# TSAC_Logic.net
KiCad netlist of a schematic drawn in Altium Designer
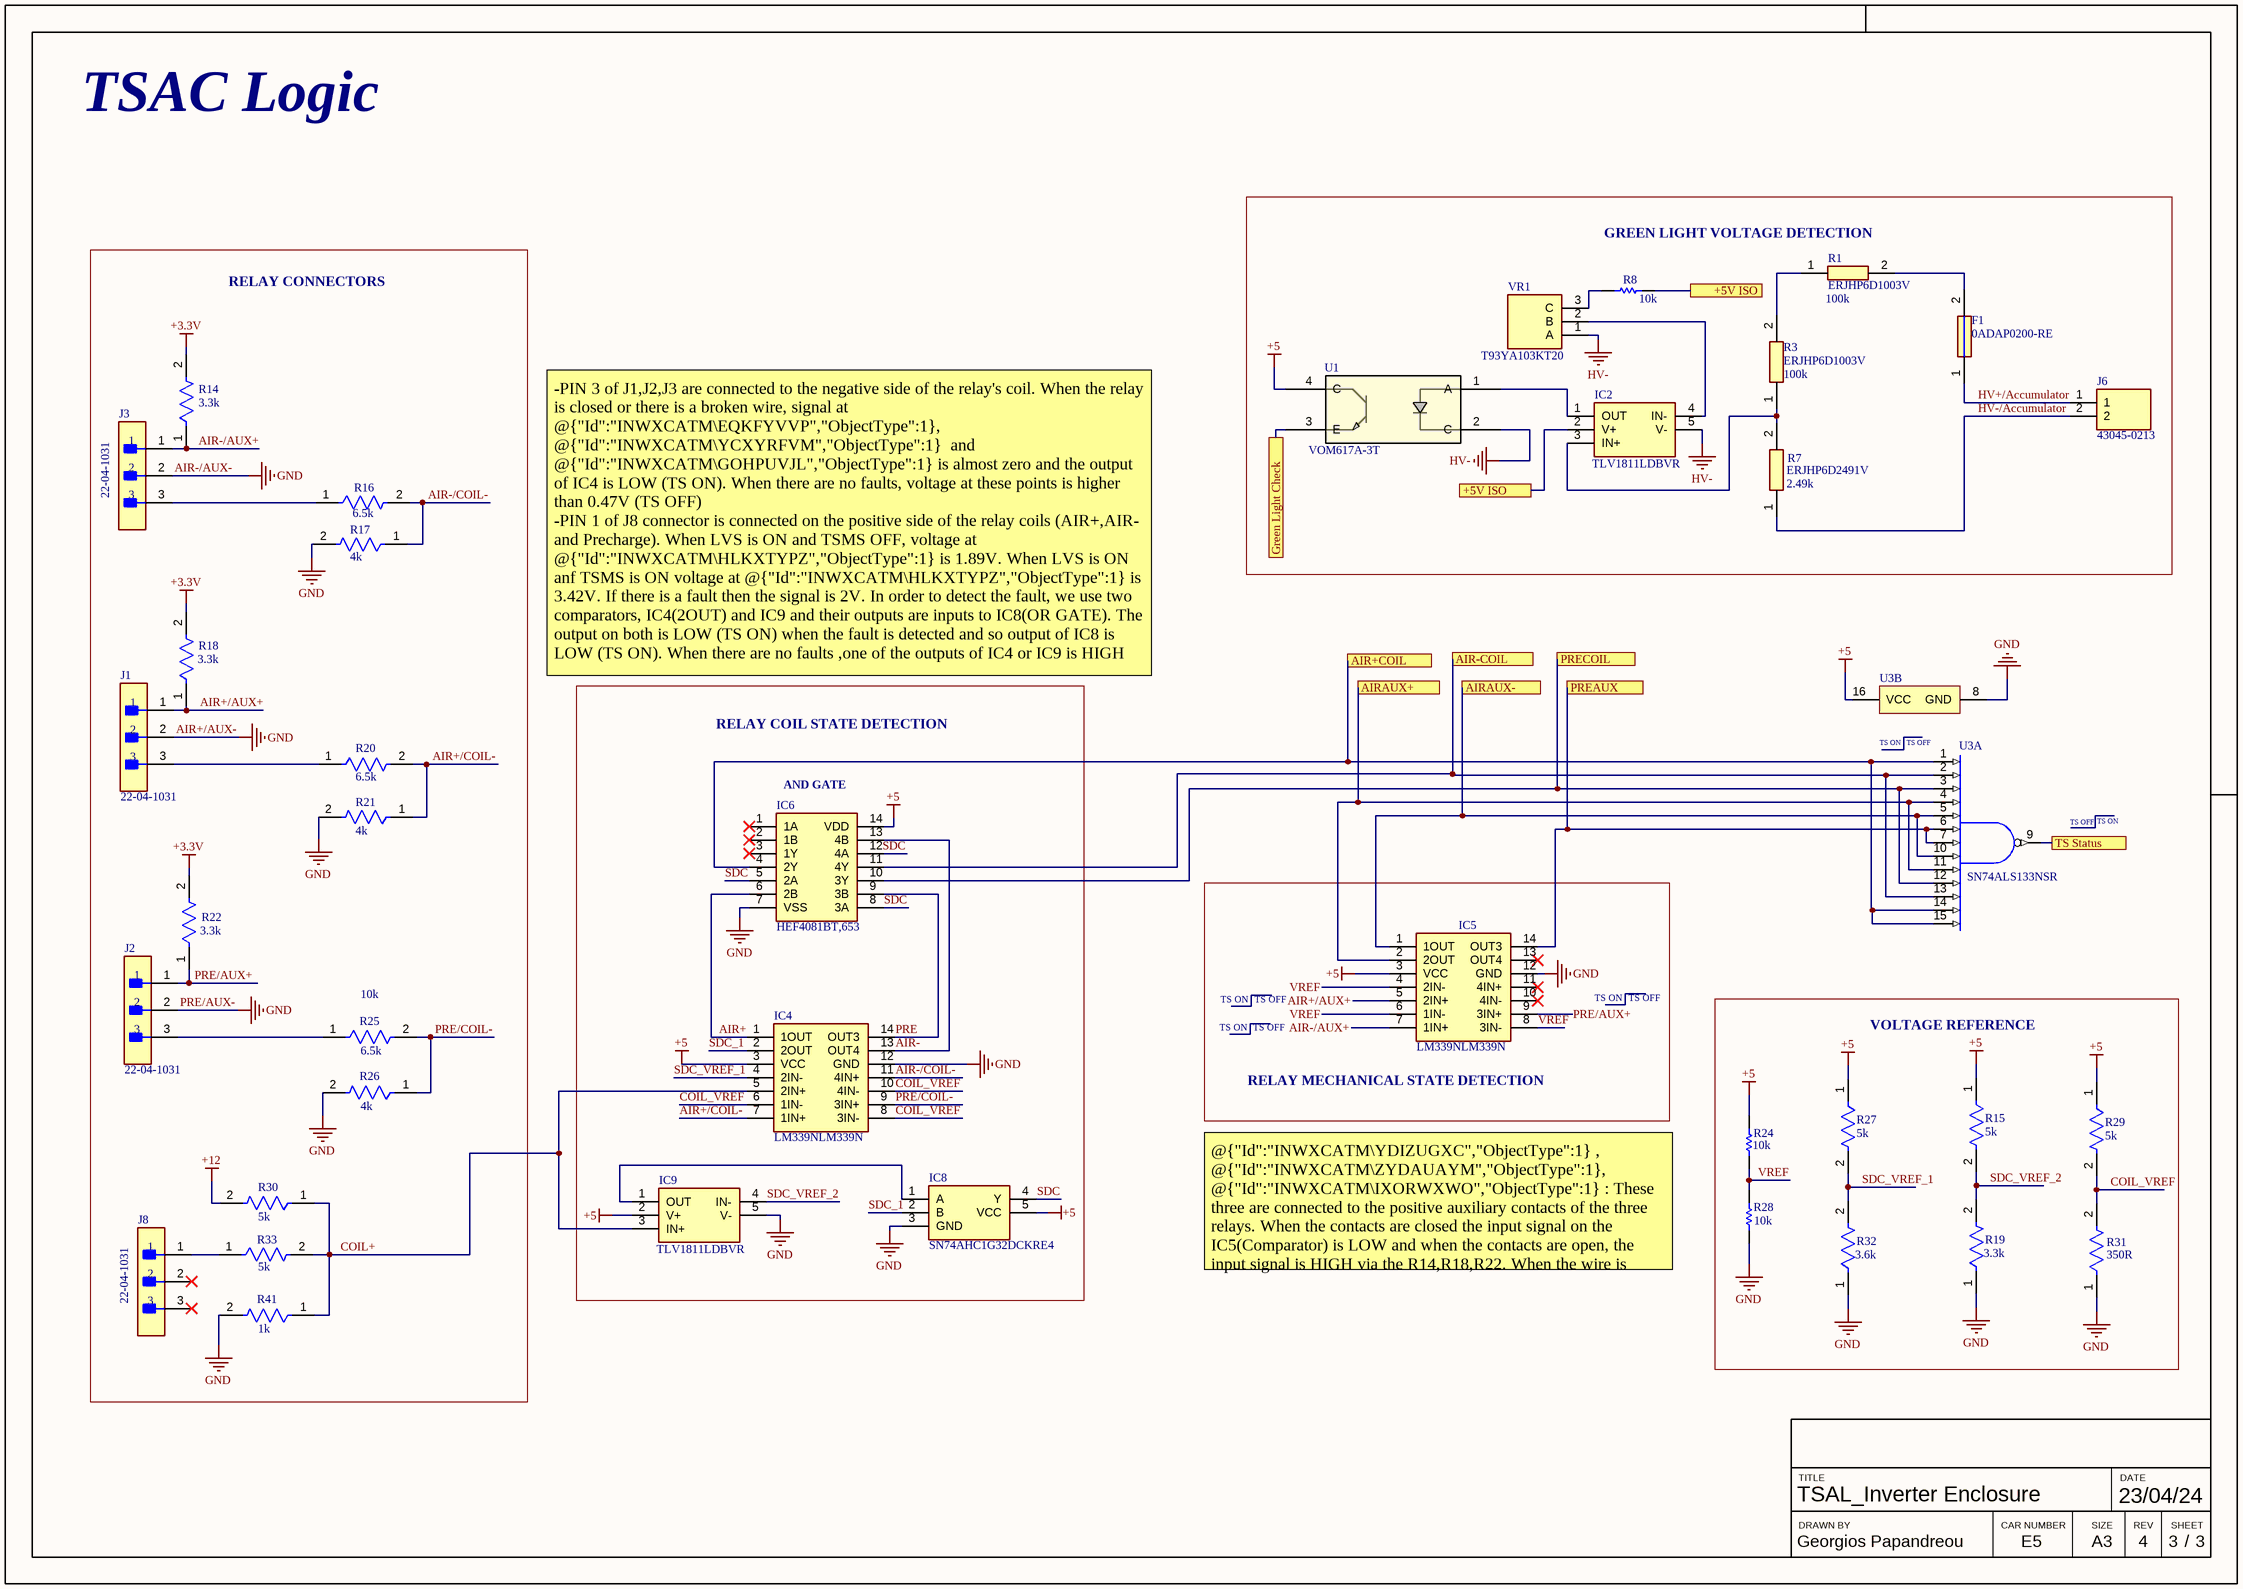
[diagram p0: TSAC_Logic.SchDoc]

(export (version "E")
  (design (tool "Eeschema 10.0.6"))
  (components
    (comp (ref "F1")
      (value "0ADAP0200-RE")
      (footprint "SamacSys:0ADAP0200RE")
      (description "Fuse")
      (fields (field (name "MOUSER PART NUMBER") "530-0ADAP0200-RE"))
      (libsource (lib "*") (part "0ADAP0200-RE"))
    )
    (comp (ref "IC2")
      (value "TLV1811LDBVR")
      (footprint "SamacSys:SOT95P280X145-5N")
      (description "Integrated Circuit")
      (fields (field (name "MOUSER PART NUMBER") "595-TLV1811LDBVR"))
      (libsource (lib "*") (part "TLV1811LDBVR"))
    )
    (comp (ref "IC4")
      (value "LM339NLM339N")
      (footprint "SamacSys:DIP794W53P254L1930H508Q14N")
      (description "Integrated Circuit")
      (fields
        (field (name "MANUFACTURER_PART_NUMBER") "LM339N")
        (field (name "MOUSER PART NUMBER") "595-LM339N")
      )
      (libsource (lib "*") (part "LM339N"))
    )
    (comp (ref "IC5")
      (value "LM339NLM339N")
      (footprint "SamacSys:DIP794W53P254L1930H508Q14N")
      (description "Integrated Circuit")
      (fields
        (field (name "MANUFACTURER_PART_NUMBER") "LM339N")
        (field (name "MOUSER PART NUMBER") "595-LM339N")
      )
      (libsource (lib "*") (part "LM339N"))
    )
    (comp (ref "IC6")
      (value "HEF4081BT,653")
      (footprint "SamacSys:SOIC127P600X175-14N")
      (description "Integrated Circuit")
      (fields (field (name "MOUSER PART NUMBER") "771-HEF4081BTD-T"))
      (libsource (lib "*") (part "HEF4081BT,653"))
    )
    (comp (ref "IC8")
      (value "SN74AHC1G32DCKRE4")
      (footprint "SamacSys:SOT65P210X110-5N")
      (description "Integrated Circuit")
      (fields (field (name "MOUSER PART NUMBER") "595-74AHC1G32DCKRE4"))
      (libsource (lib "*") (part "SN74AHC1G32DCKRE4"))
    )
    (comp (ref "IC9")
      (value "TLV1811LDBVR")
      (footprint "SamacSys:SOT95P280X145-5N")
      (description "Integrated Circuit")
      (fields (field (name "MOUSER PART NUMBER") "595-TLV1811LDBVR"))
      (libsource (lib "*") (part "TLV1811LDBVR"))
    )
    (comp (ref "J1")
      (value "22-04-1031")
      (footprint "FP-22-04-1031-MFG")
      (description "CONN HEADER VERT 3POS 2.5MM")
      (libsource (lib "Altium Content Vault") (part "0d3f023dd272f625e17a2be33dea85f"))
    )
    (comp (ref "J2")
      (value "22-04-1031")
      (footprint "FP-22-04-1031-MFG")
      (description "CONN HEADER VERT 3POS 2.5MM")
      (libsource (lib "Altium Content Vault") (part "0d3f023dd272f625e17a2be33dea85f"))
    )
    (comp (ref "J3")
      (value "22-04-1031")
      (footprint "FP-22-04-1031-MFG")
      (description "CONN HEADER VERT 3POS 2.5MM")
      (libsource (lib "Altium Content Vault") (part "0d3f023dd272f625e17a2be33dea85f"))
    )
    (comp (ref "J6")
      (value "43045-0213")
      (footprint "SamacSys:43045-02YY_121314")
      (description "Connector")
      (fields (field (name "MOUSER PART NUMBER") "538-43045-0213"))
      (libsource (lib "*") (part "43045-0213"))
    )
    (comp (ref "J8")
      (value "22-04-1031")
      (footprint "FP-22-04-1031-MFG")
      (description "CONN HEADER VERT 3POS 2.5MM")
      (libsource (lib "Altium Content Vault") (part "0d3f023dd272f625e17a2be33dea85f"))
    )
    (comp (ref "R1")
      (value "ERJHP6D1003V")
      (footprint "SamacSys:ERJHP6D1000V")
      (description "Resistor")
      (libsource (lib "") (part "ERJHP6D1003V_1"))
    )
    (comp (ref "R3")
      (value "ERJHP6D1003V")
      (footprint "SamacSys:ERJHP6D1000V")
      (description "Resistor")
      (libsource (lib "*") (part "ERJHP6D1003V"))
    )
    (comp (ref "R7")
      (value "ERJHP6D2491V")
      (footprint "SamacSys:ERJHP6D1000V")
      (description "Resistor")
      (libsource (lib "*") (part "ERJHP6D2491V"))
    )
    (comp (ref "R8")
      (value "CRCW080510K0FKEC")
      (footprint "RESC2013X50X30ML20T20")
      (fields (field (name "MANUFACTURER") "Vishay Dale"))
      (libsource (lib "Altium Content Vault") (part "RES"))
    )
    (comp (ref "R14")
      (value "CRCW08053K30FKEC")
      (footprint "FP-CRCW0805-e3-MFG")
      (description "RES Thick Film, 3.3kΩ, 1%, 0.125W, 100ppm/°C, 0805")
      (fields (field (name "TOLERANCE") "1%"))
      (libsource (lib "Altium Content Vault") (part "1029c3af85768c4190bb7ad29bc67b5"))
    )
    (comp (ref "R15")
      (value "CRCW080520K0JNEB")
      (footprint "FP-CRCW0805-e3-IPC_B")
      (description "RES Thick Film, 20kΩ, 5%, 0.125W, 200ppm/°C, 0805")
      (fields (field (name "TOLERANCE") "5%"))
      (libsource (lib "Altium Content Vault") (part "1029c3af85768c4190bb7ad29bc67b5"))
    )
    (comp (ref "R16")
      (value "CRCW120610K0FKEA")
      (footprint "FP-CRCW1206-e3-IPC_C")
      (description "RES Thick Film, 10kΩ, 1%, 0.25W, 100ppm/°C, 1206")
      (fields (field (name "TOLERANCE") "1%"))
      (libsource (lib "Altium Content Vault") (part "1029c3af85768c4190bb7ad29bc67b5"))
    )
    (comp (ref "R17")
      (value "RN732BTTD4001B25")
      (footprint "FP-RN732B-IPC_C")
      (description "4kΩ ±0.1% 0.125W, 1/8W Chip Resistor 1206 (3216 Metric) Moisture Resistant Thin Film")
      (fields (field (name "TOLERANCE") "0.1%"))
      (libsource (lib "Altium Content Vault") (part "1029c3af85768c4190bb7ad29bc67b5"))
    )
    (comp (ref "R18")
      (value "CRCW08053K30FKEC")
      (footprint "FP-CRCW0805-e3-MFG")
      (description "RES Thick Film, 3.3kΩ, 1%, 0.125W, 100ppm/°C, 0805")
      (fields (field (name "TOLERANCE") "1%"))
      (libsource (lib "Altium Content Vault") (part "1029c3af85768c4190bb7ad29bc67b5"))
    )
    (comp (ref "R19")
      (value "CRCW120610K0FKEA")
      (footprint "FP-CRCW1206-e3-IPC_C")
      (description "RES Thick Film, 10kΩ, 1%, 0.25W, 100ppm/°C, 1206")
      (fields (field (name "TOLERANCE") "1%"))
      (libsource (lib "Altium Content Vault") (part "1029c3af85768c4190bb7ad29bc67b5"))
    )
    (comp (ref "R20")
      (value "CRCW120610K0FKEA")
      (footprint "FP-CRCW1206-e3-IPC_C")
      (description "RES Thick Film, 10kΩ, 1%, 0.25W, 100ppm/°C, 1206")
      (fields (field (name "TOLERANCE") "1%"))
      (libsource (lib "Altium Content Vault") (part "1029c3af85768c4190bb7ad29bc67b5"))
    )
    (comp (ref "R21")
      (value "RN732BTTD4001B25")
      (footprint "FP-RN732B-IPC_C")
      (description "4kΩ ±0.1% 0.125W, 1/8W Chip Resistor 1206 (3216 Metric) Moisture Resistant Thin Film")
      (fields (field (name "TOLERANCE") "0.1%"))
      (libsource (lib "Altium Content Vault") (part "1029c3af85768c4190bb7ad29bc67b5"))
    )
    (comp (ref "R22")
      (value "CRCW08053K30FKEC")
      (footprint "FP-CRCW0805-e3-MFG")
      (description "RES Thick Film, 3.3kΩ, 1%, 0.125W, 100ppm/°C, 0805")
      (fields (field (name "TOLERANCE") "1%"))
      (libsource (lib "Altium Content Vault") (part "1029c3af85768c4190bb7ad29bc67b5"))
    )
    (comp (ref "R24")
      (value "CRCW080510K0FKEC")
      (footprint "RESC2013X50X30ML20T20")
      (fields (field (name "MANUFACTURER") "Vishay Dale"))
      (libsource (lib "Altium Content Vault") (part "RES"))
    )
    (comp (ref "R25")
      (value "CRCW120610K0FKEA")
      (footprint "FP-CRCW1206-e3-IPC_C")
      (description "RES Thick Film, 10kΩ, 1%, 0.25W, 100ppm/°C, 1206")
      (fields (field (name "TOLERANCE") "1%"))
      (libsource (lib "Altium Content Vault") (part "1029c3af85768c4190bb7ad29bc67b5"))
    )
    (comp (ref "R26")
      (value "RN732BTTD4001B25")
      (footprint "FP-RN732B-IPC_C")
      (description "4kΩ ±0.1% 0.125W, 1/8W Chip Resistor 1206 (3216 Metric) Moisture Resistant Thin Film")
      (fields (field (name "TOLERANCE") "0.1%"))
      (libsource (lib "Altium Content Vault") (part "1029c3af85768c4190bb7ad29bc67b5"))
    )
    (comp (ref "R27")
      (value "CRCW080520K0JNEB")
      (footprint "FP-CRCW0805-e3-IPC_B")
      (description "RES Thick Film, 20kΩ, 5%, 0.125W, 200ppm/°C, 0805")
      (fields (field (name "TOLERANCE") "5%"))
      (libsource (lib "Altium Content Vault") (part "1029c3af85768c4190bb7ad29bc67b5"))
    )
    (comp (ref "R28")
      (value "CRCW080510K0FKEC")
      (footprint "RESC2013X50X30ML20T20")
      (fields (field (name "MANUFACTURER") "Vishay Dale"))
      (libsource (lib "Altium Content Vault") (part "RES"))
    )
    (comp (ref "R29")
      (value "CRCW080520K0JNEB")
      (footprint "FP-CRCW0805-e3-IPC_B")
      (description "RES Thick Film, 20kΩ, 5%, 0.125W, 200ppm/°C, 0805")
      (fields (field (name "TOLERANCE") "5%"))
      (libsource (lib "Altium Content Vault") (part "1029c3af85768c4190bb7ad29bc67b5"))
    )
    (comp (ref "R30")
      (value "CRCW080520K0JNEB")
      (footprint "FP-CRCW0805-e3-IPC_B")
      (description "RES Thick Film, 20kΩ, 5%, 0.125W, 200ppm/°C, 0805")
      (fields (field (name "TOLERANCE") "5%"))
      (libsource (lib "Altium Content Vault") (part "1029c3af85768c4190bb7ad29bc67b5"))
    )
    (comp (ref "R31")
      (value "MCA12060D8000BP500")
      (footprint "FP-MCA1206-IPC_C")
      (description "Res MC Precision Thin Film 1206 800Ω 0.1% 0.25W ±25ppm/°C Molded Paper T/R")
      (fields (field (name "TOLERANCE") "0.1%"))
      (libsource (lib "Altium Content Vault") (part "1029c3af85768c4190bb7ad29bc67b5"))
    )
    (comp (ref "R32")
      (value "CRCW120610K0FKEA")
      (footprint "FP-CRCW1206-e3-IPC_C")
      (description "RES Thick Film, 10kΩ, 1%, 0.25W, 100ppm/°C, 1206")
      (fields (field (name "TOLERANCE") "1%"))
      (libsource (lib "Altium Content Vault") (part "1029c3af85768c4190bb7ad29bc67b5"))
    )
    (comp (ref "R33")
      (value "CRCW120610K0FKEA")
      (footprint "FP-CRCW1206-e3-IPC_C")
      (description "RES Thick Film, 10kΩ, 1%, 0.25W, 100ppm/°C, 1206")
      (fields (field (name "TOLERANCE") "1%"))
      (libsource (lib "Altium Content Vault") (part "1029c3af85768c4190bb7ad29bc67b5"))
    )
    (comp (ref "R41")
      (value "RN732BTTD4001B25")
      (footprint "FP-RN732B-IPC_C")
      (description "4kΩ ±0.1% 0.125W, 1/8W Chip Resistor 1206 (3216 Metric) Moisture Resistant Thin Film")
      (fields (field (name "TOLERANCE") "0.1%"))
      (libsource (lib "Altium Content Vault") (part "1029c3af85768c4190bb7ad29bc67b5"))
    )
    (comp (ref "U1")
      (value "VOM617A-3T")
      (footprint "SMD-4_VOM617A_VIS")
      (description "VOM617A-3T Transistor Output Optocoupler, 1-Element, 3750V Isolation")
      (libsource (lib "Altium Content Vault") (part "VOM617A-3T"))
    )
    (comp (ref "U3")
      (value "SN74ALS133NSR")
      (footprint "NS0016A_M")
      (description "13-Input Positive-NAND Gates, NS0016A, LARGE T&R")
      (fields
        (field (name "GENERIC PART NUMBER") "SN74ALS133")
        (field (name "MANUFACTURER") "Texas Instruments")
      )
      (libsource (lib "Altium Content Vault") (part "TI-SNX4ALS133-16"))
    )
    (comp (ref "VR1")
      (value "T93YA103KT20")
      (footprint "SamacSys:T93YA5K10")
      (description "Variable Resistor")
      (fields (field (name "MOUSER PART NUMBER") "72-T93YA-10K"))
      (libsource (lib "*") (part "T93YA103KT20"))
    )
  )
  (nets
    (net (code "1") (name "+3.3V") (class "Default")
      (node (ref "R14") (pin "2") (pinfunction "2_2") (pintype "passive"))
      (node (ref "R18") (pin "2") (pinfunction "2_2") (pintype "passive"))
      (node (ref "R22") (pin "2") (pinfunction "2_2") (pintype "passive"))
    )
    (net (code "2") (name "+5") (class "Default")
      (node (ref "IC4") (pin "3") (pinfunction "VCC_3") (pintype "passive"))
      (node (ref "IC5") (pin "3") (pinfunction "VCC_3") (pintype "passive"))
      (node (ref "IC6") (pin "14") (pinfunction "VDD_14") (pintype "passive"))
      (node (ref "IC8") (pin "5") (pinfunction "VCC_5") (pintype "passive"))
      (node (ref "IC9") (pin "2") (pinfunction "V+_2") (pintype "passive"))
      (node (ref "R15") (pin "1") (pinfunction "1_1") (pintype "passive"))
      (node (ref "R24") (pin "2") (pinfunction "2_2") (pintype "passive"))
      (node (ref "R27") (pin "1") (pinfunction "1_1") (pintype "passive"))
      (node (ref "R29") (pin "1") (pinfunction "1_1") (pintype "passive"))
      (node (ref "U1") (pin "4") (pinfunction "C_4") (pintype "passive"))
      (node (ref "U3") (pin "16") (pinfunction "VCC_16") (pintype "power_in"))
    )
    (net (code "3") (name "+12") (class "Default")
      (node (ref "R30") (pin "2") (pinfunction "2_2") (pintype "passive"))
    )
    (net (code "4") (name "/+5V ISO") (class "Default")
      (node (ref "IC2") (pin "2") (pinfunction "V+_2") (pintype "passive"))
      (node (ref "R8") (pin "1") (pinfunction "1_1") (pintype "passive"))
    )
    (net (code "5") (name "/AIR+") (class "Default")
      (node (ref "IC4") (pin "1") (pinfunction "1OUT_1") (pintype "passive"))
      (node (ref "IC6") (pin "6") (pinfunction "2B_6") (pintype "passive"))
    )
    (net (code "6") (name "/AIR+COIL") (class "Default")
      (node (ref "IC6") (pin "4") (pinfunction "2Y_4") (pintype "passive"))
      (node (ref "U3") (pin "1") (pinfunction "A_1") (pintype "input"))
      (node (ref "U3") (pin "14") (pinfunction "L_14") (pintype "input"))
      (node (ref "U3") (pin "15") (pinfunction "M_15") (pintype "input"))
    )
    (net (code "7") (name "/AIR+{slash}AUX+") (class "Default")
      (node (ref "IC5") (pin "5") (pinfunction "2IN+_5") (pintype "passive"))
      (node (ref "J1") (pin "1") (pinfunction "1_1") (pintype "passive"))
      (node (ref "R18") (pin "1") (pinfunction "1_1") (pintype "passive"))
    )
    (net (code "8") (name "/AIR+{slash}COIL-") (class "Default")
      (node (ref "IC4") (pin "7") (pinfunction "1IN+_7") (pintype "passive"))
      (node (ref "R20") (pin "2") (pinfunction "2_2") (pintype "passive"))
      (node (ref "R21") (pin "1") (pinfunction "1_1") (pintype "passive"))
    )
    (net (code "9") (name "/AIR-") (class "Default")
      (node (ref "IC4") (pin "13") (pinfunction "OUT4_13") (pintype "passive"))
      (node (ref "IC6") (pin "13") (pinfunction "4B_13") (pintype "passive"))
    )
    (net (code "10") (name "/AIR-COIL") (class "Default")
      (node (ref "IC6") (pin "11") (pinfunction "4Y_11") (pintype "passive"))
      (node (ref "U3") (pin "13") (pinfunction "K_13") (pintype "input"))
      (node (ref "U3") (pin "2") (pinfunction "B_2") (pintype "input"))
    )
    (net (code "11") (name "/AIR-{slash}AUX+") (class "Default")
      (node (ref "IC5") (pin "7") (pinfunction "1IN+_7") (pintype "passive"))
      (node (ref "J3") (pin "1") (pinfunction "1_1") (pintype "passive"))
      (node (ref "R14") (pin "1") (pinfunction "1_1") (pintype "passive"))
    )
    (net (code "12") (name "/AIR-{slash}COIL-") (class "Default")
      (node (ref "IC4") (pin "11") (pinfunction "4IN+_11") (pintype "passive"))
      (node (ref "R16") (pin "2") (pinfunction "2_2") (pintype "passive"))
      (node (ref "R17") (pin "1") (pinfunction "1_1") (pintype "passive"))
    )
    (net (code "13") (name "/AIRAUX+") (class "Default")
      (node (ref "IC5") (pin "2") (pinfunction "2OUT_2") (pintype "passive"))
      (node (ref "U3") (pin "11") (pinfunction "I_11") (pintype "input"))
      (node (ref "U3") (pin "4") (pinfunction "D_4") (pintype "input"))
    )
    (net (code "14") (name "/AIRAUX-") (class "Default")
      (node (ref "IC5") (pin "1") (pinfunction "1OUT_1") (pintype "passive"))
      (node (ref "U3") (pin "10") (pinfunction "H_10") (pintype "input"))
      (node (ref "U3") (pin "5") (pinfunction "E_5") (pintype "input"))
    )
    (net (code "15") (name "/COIL+") (class "Default")
      (node (ref "IC4") (pin "5") (pinfunction "2IN+_5") (pintype "passive"))
      (node (ref "IC9") (pin "3") (pinfunction "IN+_3") (pintype "passive"))
      (node (ref "R30") (pin "1") (pinfunction "1_1") (pintype "passive"))
      (node (ref "R33") (pin "2") (pinfunction "2_2") (pintype "passive"))
      (node (ref "R41") (pin "1") (pinfunction "1_1") (pintype "passive"))
    )
    (net (code "16") (name "/COIL_VREF") (class "Default")
      (node (ref "IC4") (pin "10") (pinfunction "4IN-_10") (pintype "passive"))
      (node (ref "IC4") (pin "6") (pinfunction "1IN-_6") (pintype "passive"))
      (node (ref "IC4") (pin "8") (pinfunction "3IN-_8") (pintype "passive"))
      (node (ref "R29") (pin "2") (pinfunction "2_2") (pintype "passive"))
      (node (ref "R31") (pin "2") (pinfunction "2_2") (pintype "passive"))
    )
    (net (code "17") (name "/Green Light Check") (class "Default")
      (node (ref "U1") (pin "3") (pinfunction "E_3") (pintype "passive"))
    )
    (net (code "18") (name "/HV+{slash}Accumulator") (class "Default")
      (node (ref "F1") (pin "1") (pinfunction "1_1") (pintype "passive"))
      (node (ref "J6") (pin "1") (pinfunction "1_1") (pintype "passive"))
    )
    (net (code "19") (name "/HV-{slash}Accumulator") (class "Default")
      (node (ref "J6") (pin "2") (pinfunction "2_2") (pintype "passive"))
      (node (ref "R7") (pin "1") (pinfunction "1_1") (pintype "passive"))
    )
    (net (code "20") (name "/PRE") (class "Default")
      (node (ref "IC4") (pin "14") (pinfunction "OUT3_14") (pintype "passive"))
      (node (ref "IC6") (pin "9") (pinfunction "3B_9") (pintype "passive"))
    )
    (net (code "21") (name "/PREAUX") (class "Default")
      (node (ref "IC5") (pin "14") (pinfunction "OUT3_14") (pintype "passive"))
      (node (ref "U3") (pin "6") (pinfunction "F_6") (pintype "input"))
      (node (ref "U3") (pin "7") (pinfunction "G_7") (pintype "input"))
    )
    (net (code "22") (name "/PRECOIL") (class "Default")
      (node (ref "IC6") (pin "10") (pinfunction "3Y_10") (pintype "passive"))
      (node (ref "U3") (pin "12") (pinfunction "J_12") (pintype "input"))
      (node (ref "U3") (pin "3") (pinfunction "C_3") (pintype "input"))
    )
    (net (code "23") (name "/PRE{slash}AUX+") (class "Default")
      (node (ref "IC5") (pin "9") (pinfunction "3IN+_9") (pintype "passive"))
      (node (ref "J2") (pin "1") (pinfunction "1_1") (pintype "passive"))
      (node (ref "R22") (pin "1") (pinfunction "1_1") (pintype "passive"))
    )
    (net (code "24") (name "/PRE{slash}COIL-") (class "Default")
      (node (ref "IC4") (pin "9") (pinfunction "3IN+_9") (pintype "passive"))
      (node (ref "R25") (pin "2") (pinfunction "2_2") (pintype "passive"))
      (node (ref "R26") (pin "1") (pinfunction "1_1") (pintype "passive"))
    )
    (net (code "25") (name "/SDC") (class "Default")
      (node (ref "IC6") (pin "12") (pinfunction "4A_12") (pintype "passive"))
      (node (ref "IC6") (pin "5") (pinfunction "2A_5") (pintype "passive"))
      (node (ref "IC6") (pin "8") (pinfunction "3A_8") (pintype "passive"))
      (node (ref "IC8") (pin "4") (pinfunction "Y_4") (pintype "passive"))
    )
    (net (code "26") (name "/SDC_1") (class "Default")
      (node (ref "IC4") (pin "2") (pinfunction "2OUT_2") (pintype "passive"))
      (node (ref "IC8") (pin "2") (pinfunction "B_2") (pintype "passive"))
    )
    (net (code "27") (name "/SDC_VREF_1") (class "Default")
      (node (ref "IC4") (pin "4") (pinfunction "2IN-_4") (pintype "passive"))
      (node (ref "R27") (pin "2") (pinfunction "2_2") (pintype "passive"))
      (node (ref "R32") (pin "2") (pinfunction "2_2") (pintype "passive"))
    )
    (net (code "28") (name "/SDC_VREF_2") (class "Default")
      (node (ref "IC9") (pin "4") (pinfunction "IN-_4") (pintype "passive"))
      (node (ref "R15") (pin "2") (pinfunction "2_2") (pintype "passive"))
      (node (ref "R19") (pin "2") (pinfunction "2_2") (pintype "passive"))
    )
    (net (code "29") (name "/TS Status") (class "Default")
      (node (ref "U3") (pin "9") (pinfunction "Y_9") (pintype "output"))
    )
    (net (code "30") (name "/VREF") (class "Default")
      (node (ref "IC5") (pin "4") (pinfunction "2IN-_4") (pintype "passive"))
      (node (ref "IC5") (pin "6") (pinfunction "1IN-_6") (pintype "passive"))
      (node (ref "IC5") (pin "8") (pinfunction "3IN-_8") (pintype "passive"))
      (node (ref "R24") (pin "1") (pinfunction "1_1") (pintype "passive"))
      (node (ref "R28") (pin "2") (pinfunction "2_2") (pintype "passive"))
    )
    (net (code "31") (name "GND") (class "Default")
      (node (ref "IC4") (pin "12") (pinfunction "GND_12") (pintype "passive"))
      (node (ref "IC5") (pin "12") (pinfunction "GND_12") (pintype "passive"))
      (node (ref "IC6") (pin "7") (pinfunction "VSS_7") (pintype "passive"))
      (node (ref "IC8") (pin "3") (pinfunction "GND_3") (pintype "passive"))
      (node (ref "IC9") (pin "5") (pinfunction "V-_5") (pintype "passive"))
      (node (ref "J1") (pin "2") (pinfunction "2_2") (pintype "passive"))
      (node (ref "J2") (pin "2") (pinfunction "2_2") (pintype "passive"))
      (node (ref "J3") (pin "2") (pinfunction "2_2") (pintype "passive"))
      (node (ref "R17") (pin "2") (pinfunction "2_2") (pintype "passive"))
      (node (ref "R19") (pin "1") (pinfunction "1_1") (pintype "passive"))
      (node (ref "R21") (pin "2") (pinfunction "2_2") (pintype "passive"))
      (node (ref "R26") (pin "2") (pinfunction "2_2") (pintype "passive"))
      (node (ref "R28") (pin "1") (pinfunction "1_1") (pintype "passive"))
      (node (ref "R31") (pin "1") (pinfunction "1_1") (pintype "passive"))
      (node (ref "R32") (pin "1") (pinfunction "1_1") (pintype "passive"))
      (node (ref "R41") (pin "2") (pinfunction "2_2") (pintype "passive"))
      (node (ref "U3") (pin "8") (pinfunction "GND_8") (pintype "power_in"))
    )
    (net (code "32") (name "HV-") (class "Default")
      (node (ref "IC2") (pin "5") (pinfunction "V-_5") (pintype "passive"))
      (node (ref "U1") (pin "2") (pinfunction "C_2") (pintype "passive"))
      (node (ref "VR1") (pin "1") (pinfunction "A_1") (pintype "passive"))
    )
    (net (code "33") (name "Net-(F1-Pad2)") (class "Default")
      (node (ref "F1") (pin "2") (pinfunction "2_2") (pintype "passive"))
      (node (ref "R1") (pin "2") (pinfunction "2_2") (pintype "passive"))
    )
    (net (code "34") (name "Net-(IC2-IN+)") (class "Default")
      (node (ref "IC2") (pin "3") (pinfunction "IN+_3") (pintype "passive"))
      (node (ref "R3") (pin "1") (pinfunction "1_1") (pintype "passive"))
      (node (ref "R7") (pin "2") (pinfunction "2_2") (pintype "passive"))
    )
    (net (code "35") (name "Net-(IC2-IN-)") (class "Default")
      (node (ref "IC2") (pin "4") (pinfunction "IN-_4") (pintype "passive"))
      (node (ref "VR1") (pin "2") (pinfunction "B_2") (pintype "passive"))
    )
    (net (code "36") (name "Net-(IC2-OUT)") (class "Default")
      (node (ref "IC2") (pin "1") (pinfunction "OUT_1") (pintype "passive"))
      (node (ref "U1") (pin "1") (pinfunction "A_1") (pintype "passive"))
    )
    (net (code "37") (name "Net-(IC8-A)") (class "Default")
      (node (ref "IC8") (pin "1") (pinfunction "A_1") (pintype "passive"))
      (node (ref "IC9") (pin "1") (pinfunction "OUT_1") (pintype "passive"))
    )
    (net (code "38") (name "Net-(J1-Pad3)") (class "Default")
      (node (ref "J1") (pin "3") (pinfunction "3_3") (pintype "passive"))
      (node (ref "R20") (pin "1") (pinfunction "1_1") (pintype "passive"))
    )
    (net (code "39") (name "Net-(J2-Pad3)") (class "Default")
      (node (ref "J2") (pin "3") (pinfunction "3_3") (pintype "passive"))
      (node (ref "R25") (pin "1") (pinfunction "1_1") (pintype "passive"))
    )
    (net (code "40") (name "Net-(J3-Pad3)") (class "Default")
      (node (ref "J3") (pin "3") (pinfunction "3_3") (pintype "passive"))
      (node (ref "R16") (pin "1") (pinfunction "1_1") (pintype "passive"))
    )
    (net (code "41") (name "Net-(J8-Pad1)") (class "Default")
      (node (ref "J8") (pin "1") (pinfunction "1_1") (pintype "passive"))
      (node (ref "R33") (pin "1") (pinfunction "1_1") (pintype "passive"))
    )
    (net (code "42") (name "Net-(R1-Pad1)") (class "Default")
      (node (ref "R1") (pin "1") (pinfunction "1_1") (pintype "passive"))
      (node (ref "R3") (pin "2") (pinfunction "2_2") (pintype "passive"))
    )
    (net (code "43") (name "Net-(VR1-C)") (class "Default")
      (node (ref "R8") (pin "2") (pinfunction "2_2") (pintype "passive"))
      (node (ref "VR1") (pin "3") (pinfunction "C_3") (pintype "passive"))
    )
    (net (code "44") (name "unconnected-(IC5-4IN+-Pad11)") (class "Default")
      (node (ref "IC5") (pin "11") (pinfunction "4IN+_11") (pintype "passive+no_connect"))
    )
    (net (code "45") (name "unconnected-(IC5-4IN--Pad10)") (class "Default")
      (node (ref "IC5") (pin "10") (pinfunction "4IN-_10") (pintype "passive+no_connect"))
    )
    (net (code "46") (name "unconnected-(IC5-OUT4-Pad13)") (class "Default")
      (node (ref "IC5") (pin "13") (pinfunction "OUT4_13") (pintype "passive+no_connect"))
    )
    (net (code "47") (name "unconnected-(IC6-1A-Pad1)") (class "Default")
      (node (ref "IC6") (pin "1") (pinfunction "1A_1") (pintype "passive+no_connect"))
    )
    (net (code "48") (name "unconnected-(IC6-1B-Pad2)") (class "Default")
      (node (ref "IC6") (pin "2") (pinfunction "1B_2") (pintype "passive+no_connect"))
    )
    (net (code "49") (name "unconnected-(IC6-1Y-Pad3)") (class "Default")
      (node (ref "IC6") (pin "3") (pinfunction "1Y_3") (pintype "passive+no_connect"))
    )
    (net (code "50") (name "unconnected-(J8-Pad2)") (class "Default")
      (node (ref "J8") (pin "2") (pinfunction "2_2") (pintype "passive+no_connect"))
    )
    (net (code "51") (name "unconnected-(J8-Pad3)") (class "Default")
      (node (ref "J8") (pin "3") (pinfunction "3_3") (pintype "passive+no_connect"))
    )
  )
)
